# Min_Core_Display_v2.net
KiCad netlist of a schematic drawn in EAGLE
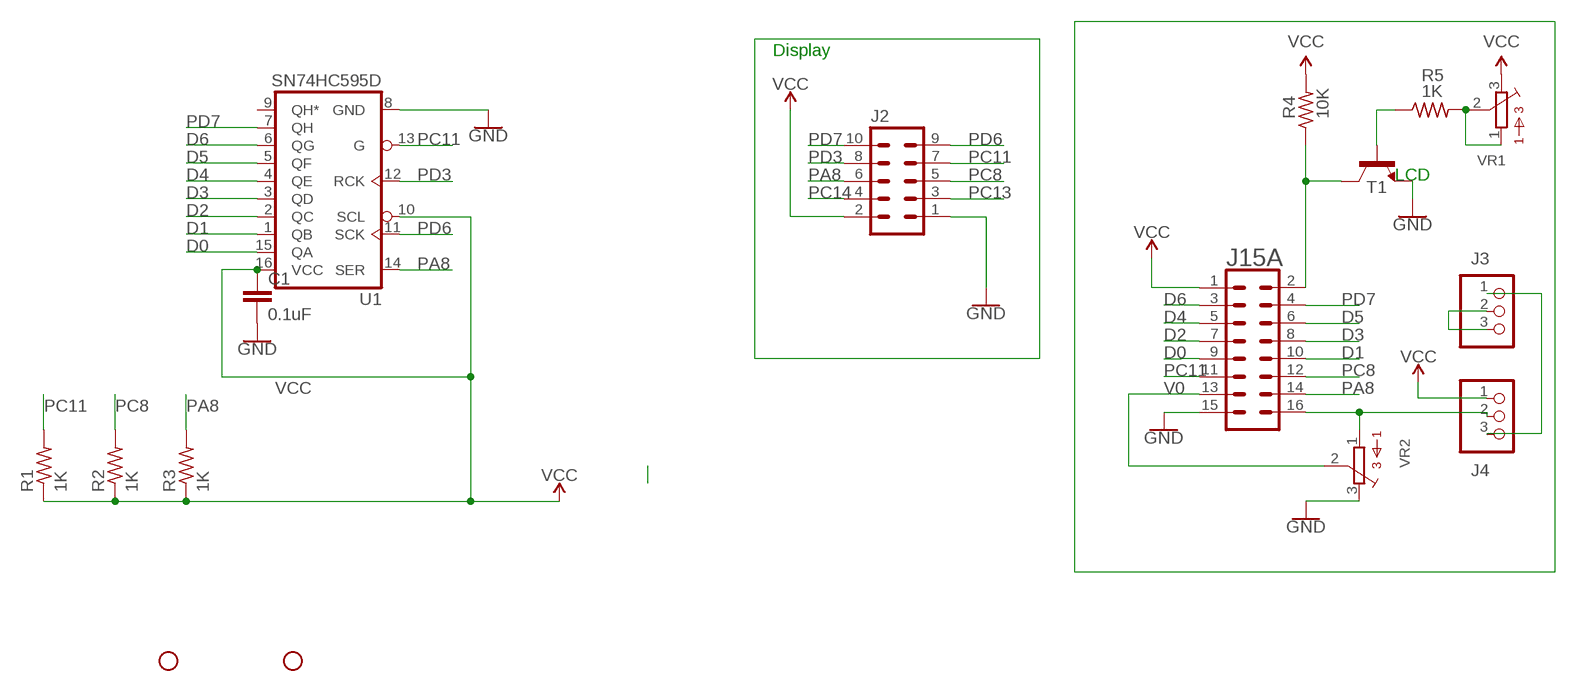
[diagram p0: schematic, sheet 1]

(export (version "E")
  (design (tool "Eeschema 10.0.6"))
  (components
    (comp (ref "C1")
      (value "0.1uF")
      (footprint "eagle-import:0603")
      (libsource (lib "eagle-import") (part "0.1UF-0603-25V-(+80/-20%)"))
    )
    (comp (ref "H2")
      (value "STAND-OFFTIGHT")
      (footprint "eagle-import:STAND-OFF-TIGHT")
      (libsource (lib "eagle-import") (part "STAND-OFFTIGHT"))
    )
    (comp (ref "H4")
      (value "STAND-OFFTIGHT")
      (footprint "eagle-import:STAND-OFF-TIGHT")
      (libsource (lib "eagle-import") (part "STAND-OFFTIGHT"))
    )
    (comp (ref "J2")
      (value "10PIN_BACKSIDE")
      (footprint "eagle-import:10PIN_BACKSIDE")
      (libsource (lib "eagle-import") (part "10PIN_BACKSIDE"))
    )
    (comp (ref "J3")
      (value "PINHD-1X3")
      (footprint "eagle-import:1X03")
      (libsource (lib "eagle-import") (part "PINHD-1X3"))
    )
    (comp (ref "J4")
      (value "PINHD-1X3")
      (footprint "eagle-import:1X03")
      (libsource (lib "eagle-import") (part "PINHD-1X3"))
    )
    (comp (ref "J15A")
      (value "CONN_08X2_SHROUD")
      (footprint "eagle-import:2X8-SHROUDED_LOCK")
      (libsource (lib "eagle-import") (part "CONN_08X2_SHROUD"))
    )
    (comp (ref "R1")
      (value "1K")
      (footprint "eagle-import:R0603")
      (libsource (lib "eagle-import") (part "R-US_R0603"))
    )
    (comp (ref "R2")
      (value "1K")
      (footprint "eagle-import:R0603")
      (libsource (lib "eagle-import") (part "R-US_R0603"))
    )
    (comp (ref "R3")
      (value "1K")
      (footprint "eagle-import:R0603")
      (libsource (lib "eagle-import") (part "R-US_R0603"))
    )
    (comp (ref "R4")
      (value "10K")
      (footprint "eagle-import:R0603")
      (libsource (lib "eagle-import") (part "R-US_R0603"))
    )
    (comp (ref "R5")
      (value "1K")
      (footprint "eagle-import:R0603")
      (libsource (lib "eagle-import") (part "R-US_R0603"))
    )
    (comp (ref "T1")
      (value "600mA/40V")
      (footprint "eagle-import:TO-92")
      (libsource (lib "eagle-import") (part "TRANS_NPN-P2N2222A"))
    )
    (comp (ref "U1")
      (value "SN74HC595D")
      (footprint "eagle-import:SO16")
      (libsource (lib "eagle-import") (part "74595DHC"))
    )
    (comp (ref "VR1")
      (value "BOURNS_3362P_TRIMMERP")
      (footprint "eagle-import:BOURNS_3362P_TRIMMER")
      (libsource (lib "eagle-import") (part "BOURNS_3362P_TRIMMERP"))
    )
    (comp (ref "VR2")
      (value "BOURNS_3362P_TRIMMERP")
      (footprint "eagle-import:BOURNS_3362P_TRIMMER")
      (libsource (lib "eagle-import") (part "BOURNS_3362P_TRIMMERP"))
    )
  )
  (nets
    (net (code "1") (name "/D0") (class "Default")
      (node (ref "J15A") (pin "9") (pinfunction "9_9") (pintype "passive"))
      (node (ref "U1") (pin "15") (pinfunction "QA_15") (pintype "tri_state"))
    )
    (net (code "2") (name "/D1") (class "Default")
      (node (ref "J15A") (pin "10") (pinfunction "10_10") (pintype "passive"))
      (node (ref "U1") (pin "1") (pinfunction "QB_1") (pintype "tri_state"))
    )
    (net (code "3") (name "/D2") (class "Default")
      (node (ref "J15A") (pin "7") (pinfunction "7_7") (pintype "passive"))
      (node (ref "U1") (pin "2") (pinfunction "QC_2") (pintype "tri_state"))
    )
    (net (code "4") (name "/D3") (class "Default")
      (node (ref "J15A") (pin "8") (pinfunction "8_8") (pintype "passive"))
      (node (ref "U1") (pin "3") (pinfunction "QD_3") (pintype "tri_state"))
    )
    (net (code "5") (name "/D4") (class "Default")
      (node (ref "J15A") (pin "5") (pinfunction "5_5") (pintype "passive"))
      (node (ref "U1") (pin "4") (pinfunction "QE_4") (pintype "tri_state"))
    )
    (net (code "6") (name "/D5") (class "Default")
      (node (ref "J15A") (pin "6") (pinfunction "6_6") (pintype "passive"))
      (node (ref "U1") (pin "5") (pinfunction "QF_5") (pintype "tri_state"))
    )
    (net (code "7") (name "/D6") (class "Default")
      (node (ref "J15A") (pin "3") (pinfunction "3_3") (pintype "passive"))
      (node (ref "U1") (pin "6") (pinfunction "QG_6") (pintype "tri_state"))
    )
    (net (code "8") (name "/PA8") (class "Default")
      (node (ref "J15A") (pin "14") (pinfunction "14_14") (pintype "passive"))
      (node (ref "J2") (pin "6") (pinfunction "6_6") (pintype "passive"))
      (node (ref "R3") (pin "2") (pinfunction "2_2") (pintype "passive"))
      (node (ref "U1") (pin "14") (pinfunction "SER_14") (pintype "input"))
    )
    (net (code "9") (name "/PC8") (class "Default")
      (node (ref "J15A") (pin "12") (pinfunction "12_12") (pintype "passive"))
      (node (ref "J2") (pin "5") (pinfunction "5_5") (pintype "passive"))
      (node (ref "R2") (pin "2") (pinfunction "2_2") (pintype "passive"))
    )
    (net (code "10") (name "/PC11") (class "Default")
      (node (ref "J15A") (pin "11") (pinfunction "11_11") (pintype "passive"))
      (node (ref "J2") (pin "7") (pinfunction "7_7") (pintype "passive"))
      (node (ref "R1") (pin "2") (pinfunction "2_2") (pintype "passive"))
      (node (ref "U1") (pin "13") (pinfunction "G_13") (pintype "input"))
    )
    (net (code "11") (name "/PC13") (class "Default")
      (node (ref "J2") (pin "3") (pinfunction "3_3") (pintype "passive"))
    )
    (net (code "12") (name "/PC14") (class "Default")
      (node (ref "J2") (pin "4") (pinfunction "4_4") (pintype "passive"))
    )
    (net (code "13") (name "/PD3") (class "Default")
      (node (ref "J2") (pin "8") (pinfunction "8_8") (pintype "passive"))
      (node (ref "U1") (pin "12") (pinfunction "RCK_12") (pintype "input"))
    )
    (net (code "14") (name "/PD6") (class "Default")
      (node (ref "J2") (pin "9") (pinfunction "9_9") (pintype "passive"))
      (node (ref "U1") (pin "11") (pinfunction "SCK_11") (pintype "input"))
    )
    (net (code "15") (name "/PD7") (class "Default")
      (node (ref "J15A") (pin "4") (pinfunction "4_4") (pintype "passive"))
      (node (ref "J2") (pin "10") (pinfunction "10_10") (pintype "passive"))
      (node (ref "U1") (pin "7") (pinfunction "QH_7") (pintype "tri_state"))
    )
    (net (code "16") (name "/V0") (class "Default")
      (node (ref "J15A") (pin "13") (pinfunction "13_13") (pintype "passive"))
      (node (ref "VR2") (pin "2") (pinfunction "2_2") (pintype "passive"))
    )
    (net (code "17") (name "GND") (class "Default")
      (node (ref "C1") (pin "2") (pinfunction "2_2") (pintype "passive"))
      (node (ref "J15A") (pin "15") (pinfunction "15_15") (pintype "passive"))
      (node (ref "J2") (pin "1") (pinfunction "1_1") (pintype "passive"))
      (node (ref "T1") (pin "3") (pinfunction "E_3") (pintype "passive"))
      (node (ref "U1") (pin "8") (pinfunction "GND_8") (pintype "power_in"))
      (node (ref "VR2") (pin "3") (pinfunction "3_3") (pintype "passive"))
    )
    (net (code "18") (name "Net-(J3-Pad1)") (class "Default")
      (node (ref "J3") (pin "1") (pinfunction "1_1") (pintype "passive"))
      (node (ref "J4") (pin "3") (pinfunction "3_3") (pintype "passive"))
    )
    (net (code "19") (name "Net-(J3-Pad2)") (class "Default")
      (node (ref "J3") (pin "2") (pinfunction "2_2") (pintype "passive"))
      (node (ref "J3") (pin "3") (pinfunction "3_3") (pintype "passive"))
    )
    (net (code "20") (name "Net-(J15A-Pad16)") (class "Default")
      (node (ref "J15A") (pin "16") (pinfunction "16_16") (pintype "passive"))
      (node (ref "J4") (pin "2") (pinfunction "2_2") (pintype "passive"))
      (node (ref "VR2") (pin "1") (pinfunction "1_1") (pintype "passive"))
    )
    (net (code "21") (name "Net-(R5-Pad2)") (class "Default")
      (node (ref "R5") (pin "2") (pinfunction "2_2") (pintype "passive"))
      (node (ref "VR1") (pin "1") (pinfunction "1_1") (pintype "passive"))
      (node (ref "VR1") (pin "2") (pinfunction "2_2") (pintype "passive"))
    )
    (net (code "22") (name "Net-(T1-B)") (class "Default")
      (node (ref "R5") (pin "1") (pinfunction "1_1") (pintype "passive"))
      (node (ref "T1") (pin "2") (pinfunction "B_2") (pintype "passive"))
    )
    (net (code "23") (name "Net-(T1-C)") (class "Default")
      (node (ref "J15A") (pin "2") (pinfunction "2_2") (pintype "passive"))
      (node (ref "R4") (pin "1") (pinfunction "1_1") (pintype "passive"))
      (node (ref "T1") (pin "1") (pinfunction "C_1") (pintype "passive"))
    )
    (net (code "24") (name "VCC") (class "Default")
      (node (ref "C1") (pin "1") (pinfunction "1_1") (pintype "passive"))
      (node (ref "J15A") (pin "1") (pinfunction "1_1") (pintype "passive"))
      (node (ref "J2") (pin "2") (pinfunction "2_2") (pintype "passive"))
      (node (ref "J4") (pin "1") (pinfunction "1_1") (pintype "passive"))
      (node (ref "R1") (pin "1") (pinfunction "1_1") (pintype "passive"))
      (node (ref "R2") (pin "1") (pinfunction "1_1") (pintype "passive"))
      (node (ref "R3") (pin "1") (pinfunction "1_1") (pintype "passive"))
      (node (ref "R4") (pin "2") (pinfunction "2_2") (pintype "passive"))
      (node (ref "U1") (pin "10") (pinfunction "SCL_10") (pintype "input"))
      (node (ref "U1") (pin "16") (pinfunction "VCC_16") (pintype "power_in"))
      (node (ref "VR1") (pin "3") (pinfunction "3_3") (pintype "passive"))
    )
    (net (code "25") (name "unconnected-(U1-QH*-Pad9)") (class "Default")
      (node (ref "U1") (pin "9") (pinfunction "QH*_9") (pintype "tri_state"))
    )
  )
)
